# bridge_leg.net
KiCad netlist of a schematic drawn in Altium Designer
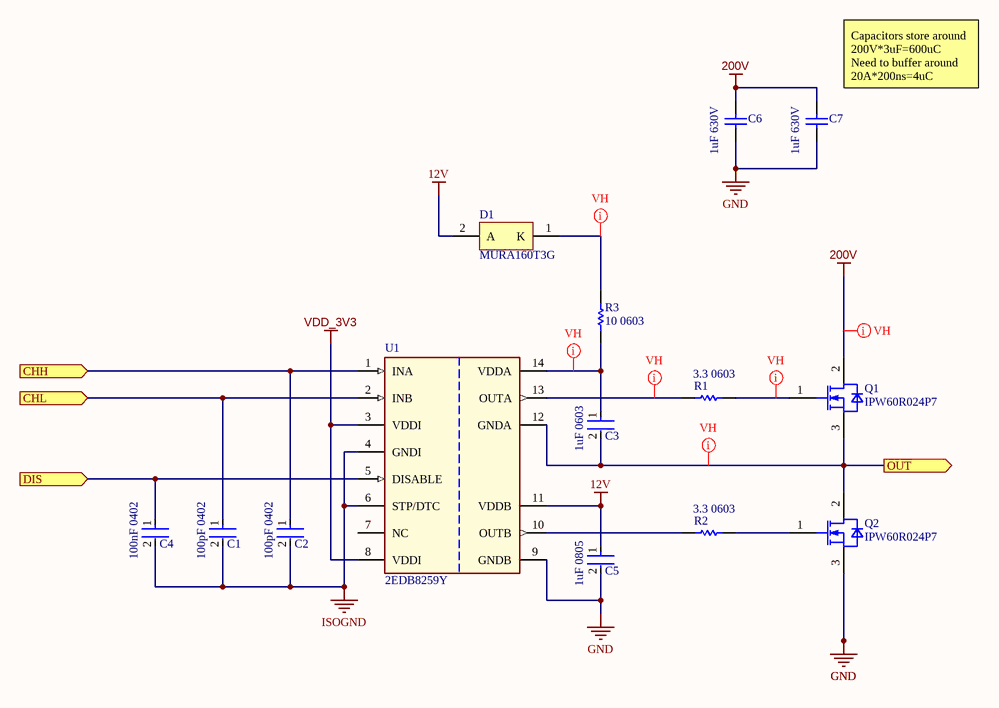
[diagram p0: bridge_leg.SchDoc]

(export (version "E")
  (design (tool "Eeschema 10.0.6"))
  (components
    (comp (ref "C1")
      (value "100pF 0402")
      (footprint "CAP 0402_1005 RF")
      (description "MLCC 0402 100pF")
      (fields (field (name "VOLTAGE") "50V") (field (name "TOLERANCE") "5%"))
      (libsource (lib "mdriver2_control") (part "b4654b650e69147ec39a6b967a45e02"))
    )
    (comp (ref "C2")
      (value "100pF 0402")
      (footprint "CAP 0402_1005 RF")
      (description "MLCC 0402 100pF")
      (fields (field (name "VOLTAGE") "50V") (field (name "TOLERANCE") "5%"))
      (libsource (lib "mdriver2_control") (part "b4654b650e69147ec39a6b967a45e02"))
    )
    (comp (ref "C3")
      (value "1uF 0603")
      (footprint "CAP 0805_2012")
      (description "MLCC 0805 1uF")
      (fields (field (name "VOLTAGE") "50V") (field (name "TOLERANCE") "5%"))
      (libsource (lib "mdriver2_control") (part "b4654b650e69147ec39a6b967a45e02"))
    )
    (comp (ref "C4")
      (value "100nF 0402")
      (footprint "CAP 0402_1005 RF")
      (description "MLCC 0402 100pF")
      (fields (field (name "VOLTAGE") "50V") (field (name "TOLERANCE") "5%"))
      (libsource (lib "mdriver2_control") (part "b4654b650e69147ec39a6b967a45e02"))
    )
    (comp (ref "C5")
      (value "1uF 0805")
      (footprint "CAP 0805_2012")
      (description "MLCC 0805 1uF")
      (fields (field (name "VOLTAGE") "50V") (field (name "TOLERANCE") "5%"))
      (libsource (lib "mdriver2_control") (part "b4654b650e69147ec39a6b967a45e02"))
    )
    (comp (ref "C6")
      (value "1uF 630V")
      (footprint "CAP 2220_5650 2.5MM")
      (description "MLCC 1Uf, 630V, Mlcc, 2220 Rohs Compliant: Yes")
      (libsource (lib "mdriver2_power_hw") (part "Capacitor_Non-Polarized"))
    )
    (comp (ref "C7")
      (value "1uF 630V")
      (footprint "CAP 2220_5650 2.5MM")
      (description "MLCC 1Uf, 630V, Mlcc, 2220 Rohs Compliant: Yes")
      (libsource (lib "mdriver2_power_hw") (part "Capacitor_Non-Polarized"))
    )
    (comp (ref "D1")
      (value "MURA160T3G")
      (footprint "ONSC-SMA-2-403D-02_V")
      (description "Surface Mount Ultrafast Power Rectifier, 2-Pin SMA, Pb-Free, Tape and Reel")
      (fields (field (name "MANUFACTURER") "On Semiconductor"))
      (libsource (lib "Altium Content Vault") (part "ONSC-D-K1A2-2_A"))
    )
    (comp (ref "Q1")
      (value "IPW60R024P7")
      (footprint "INF-PG-TO247-3")
      (description "Smart Low Side Power Switch")
      (fields (field (name "MANUFACTURER") "Infineon Technologies"))
      (libsource (lib "IPW60R024P7") (part "IPW60R024P7"))
    )
    (comp (ref "Q2")
      (value "IPW60R024P7")
      (footprint "INF-PG-TO247-3")
      (description "Smart Low Side Power Switch")
      (fields (field (name "MANUFACTURER") "Infineon Technologies"))
      (libsource (lib "IPW60R024P7") (part "IPW60R024P7"))
    )
    (comp (ref "R1")
      (value "3.3 0603")
      (footprint "RES 0603_1608")
      (description "Resistor 3.3Ohm 0603")
      (fields (field (name "PUBLISHER") "Altium Limited"))
      (libsource (lib "Miscellaneous Devices") (part "Res1"))
    )
    (comp (ref "R2")
      (value "3.3 0603")
      (footprint "RES 0603_1608")
      (description "Resistor 3.3Ohm 0603")
      (fields (field (name "PUBLISHER") "Altium Limited"))
      (libsource (lib "Miscellaneous Devices") (part "Res1"))
    )
    (comp (ref "R3")
      (value "10 0603")
      (footprint "RES 0603_1608")
      (description "Resistor 10Ohm 0603")
      (fields (field (name "PUBLISHER") "Altium Limited"))
      (libsource (lib "Miscellaneous Devices") (part "Res1"))
    )
    (comp (ref "U1")
      (value "2EDB8259Y")
      (footprint "SOIC127P600X175-16_14N-1-V")
      (description "Dual-Channel Isolated Gate Driver")
      (fields (field (name "MANUFACTURER") "Infineon Technologies"))
      (libsource (lib "2EDB8259Y") (part "2EDB8259Y"))
    )
  )
  (nets
    (net (code "1") (name "/CHH") (class "Default")
      (node (ref "C2") (pin "1") (pinfunction "1_1") (pintype "passive"))
      (node (ref "U1") (pin "1") (pinfunction "INA_1") (pintype "input"))
    )
    (net (code "2") (name "/CHL") (class "Default")
      (node (ref "C1") (pin "1") (pinfunction "1_1") (pintype "passive"))
      (node (ref "U1") (pin "2") (pinfunction "INB_2") (pintype "input"))
    )
    (net (code "3") (name "/DIS") (class "Default")
      (node (ref "C4") (pin "1") (pinfunction "1_1") (pintype "passive"))
      (node (ref "U1") (pin "5") (pinfunction "DISABLE_5") (pintype "input"))
    )
    (net (code "4") (name "/OUT") (class "Default")
      (node (ref "C3") (pin "2") (pinfunction "2_2") (pintype "passive"))
      (node (ref "Q1") (pin "3") (pinfunction "SOURCE_3") (pintype "passive"))
      (node (ref "Q2") (pin "2") (pinfunction "DRAIN_2") (pintype "passive"))
      (node (ref "U1") (pin "12") (pinfunction "GNDA_12") (pintype "power_in"))
    )
    (net (code "5") (name "12V") (class "Default")
      (node (ref "C5") (pin "1") (pinfunction "1_1") (pintype "passive"))
      (node (ref "D1") (pin "2") (pinfunction "A_2") (pintype "passive"))
      (node (ref "U1") (pin "11") (pinfunction "VDDB_11") (pintype "power_in"))
    )
    (net (code "6") (name "200V") (class "Default")
      (node (ref "C6") (pin "2") (pinfunction "2_2") (pintype "passive"))
      (node (ref "C7") (pin "2") (pinfunction "2_2") (pintype "passive"))
      (node (ref "Q1") (pin "2") (pinfunction "DRAIN_2") (pintype "passive"))
    )
    (net (code "7") (name "GND") (class "Default")
      (node (ref "C5") (pin "2") (pinfunction "2_2") (pintype "passive"))
      (node (ref "C6") (pin "1") (pinfunction "1_1") (pintype "passive"))
      (node (ref "C7") (pin "1") (pinfunction "1_1") (pintype "passive"))
      (node (ref "Q2") (pin "3") (pinfunction "SOURCE_3") (pintype "passive"))
      (node (ref "U1") (pin "9") (pinfunction "GNDB_9") (pintype "power_in"))
    )
    (net (code "8") (name "ISOGND") (class "Default")
      (node (ref "C1") (pin "2") (pinfunction "2_2") (pintype "passive"))
      (node (ref "C2") (pin "2") (pinfunction "2_2") (pintype "passive"))
      (node (ref "C4") (pin "2") (pinfunction "2_2") (pintype "passive"))
      (node (ref "U1") (pin "4") (pinfunction "GNDI_4") (pintype "power_in"))
      (node (ref "U1") (pin "6") (pinfunction "STP/DTC_6") (pintype "passive"))
    )
    (net (code "9") (name "Net-(D1-K)") (class "Default")
      (node (ref "D1") (pin "1") (pinfunction "K_1") (pintype "passive"))
      (node (ref "R3") (pin "2") (pinfunction "2_2") (pintype "passive"))
    )
    (net (code "10") (name "Net-(Q1-GATE)") (class "Default")
      (node (ref "Q1") (pin "1") (pinfunction "GATE_1") (pintype "passive"))
      (node (ref "R1") (pin "2") (pinfunction "2_2") (pintype "passive"))
    )
    (net (code "11") (name "Net-(Q2-GATE)") (class "Default")
      (node (ref "Q2") (pin "1") (pinfunction "GATE_1") (pintype "passive"))
      (node (ref "R2") (pin "2") (pinfunction "2_2") (pintype "passive"))
    )
    (net (code "12") (name "Net-(U1-OUTA)") (class "Default")
      (node (ref "R1") (pin "1") (pinfunction "1_1") (pintype "passive"))
      (node (ref "U1") (pin "13") (pinfunction "OUTA_13") (pintype "output"))
    )
    (net (code "13") (name "Net-(U1-OUTB)") (class "Default")
      (node (ref "R2") (pin "1") (pinfunction "1_1") (pintype "passive"))
      (node (ref "U1") (pin "10") (pinfunction "OUTB_10") (pintype "output"))
    )
    (net (code "14") (name "Net-(U1-VDDA)") (class "Default")
      (node (ref "C3") (pin "1") (pinfunction "1_1") (pintype "passive"))
      (node (ref "R3") (pin "1") (pinfunction "1_1") (pintype "passive"))
      (node (ref "U1") (pin "14") (pinfunction "VDDA_14") (pintype "power_in"))
    )
    (net (code "15") (name "VDD_3V3") (class "Default")
      (node (ref "U1") (pin "3") (pinfunction "VDDI_3") (pintype "power_in"))
      (node (ref "U1") (pin "8") (pinfunction "VDDI_8") (pintype "power_in"))
    )
    (net (code "16") (name "unconnected-(U1-NC-Pad7)") (class "Default")
      (node (ref "U1") (pin "7") (pinfunction "NC_7") (pintype "passive"))
    )
  )
)
